# X10_-_Main_Board_RevB.net
KiCad netlist of a schematic drawn in EAGLE
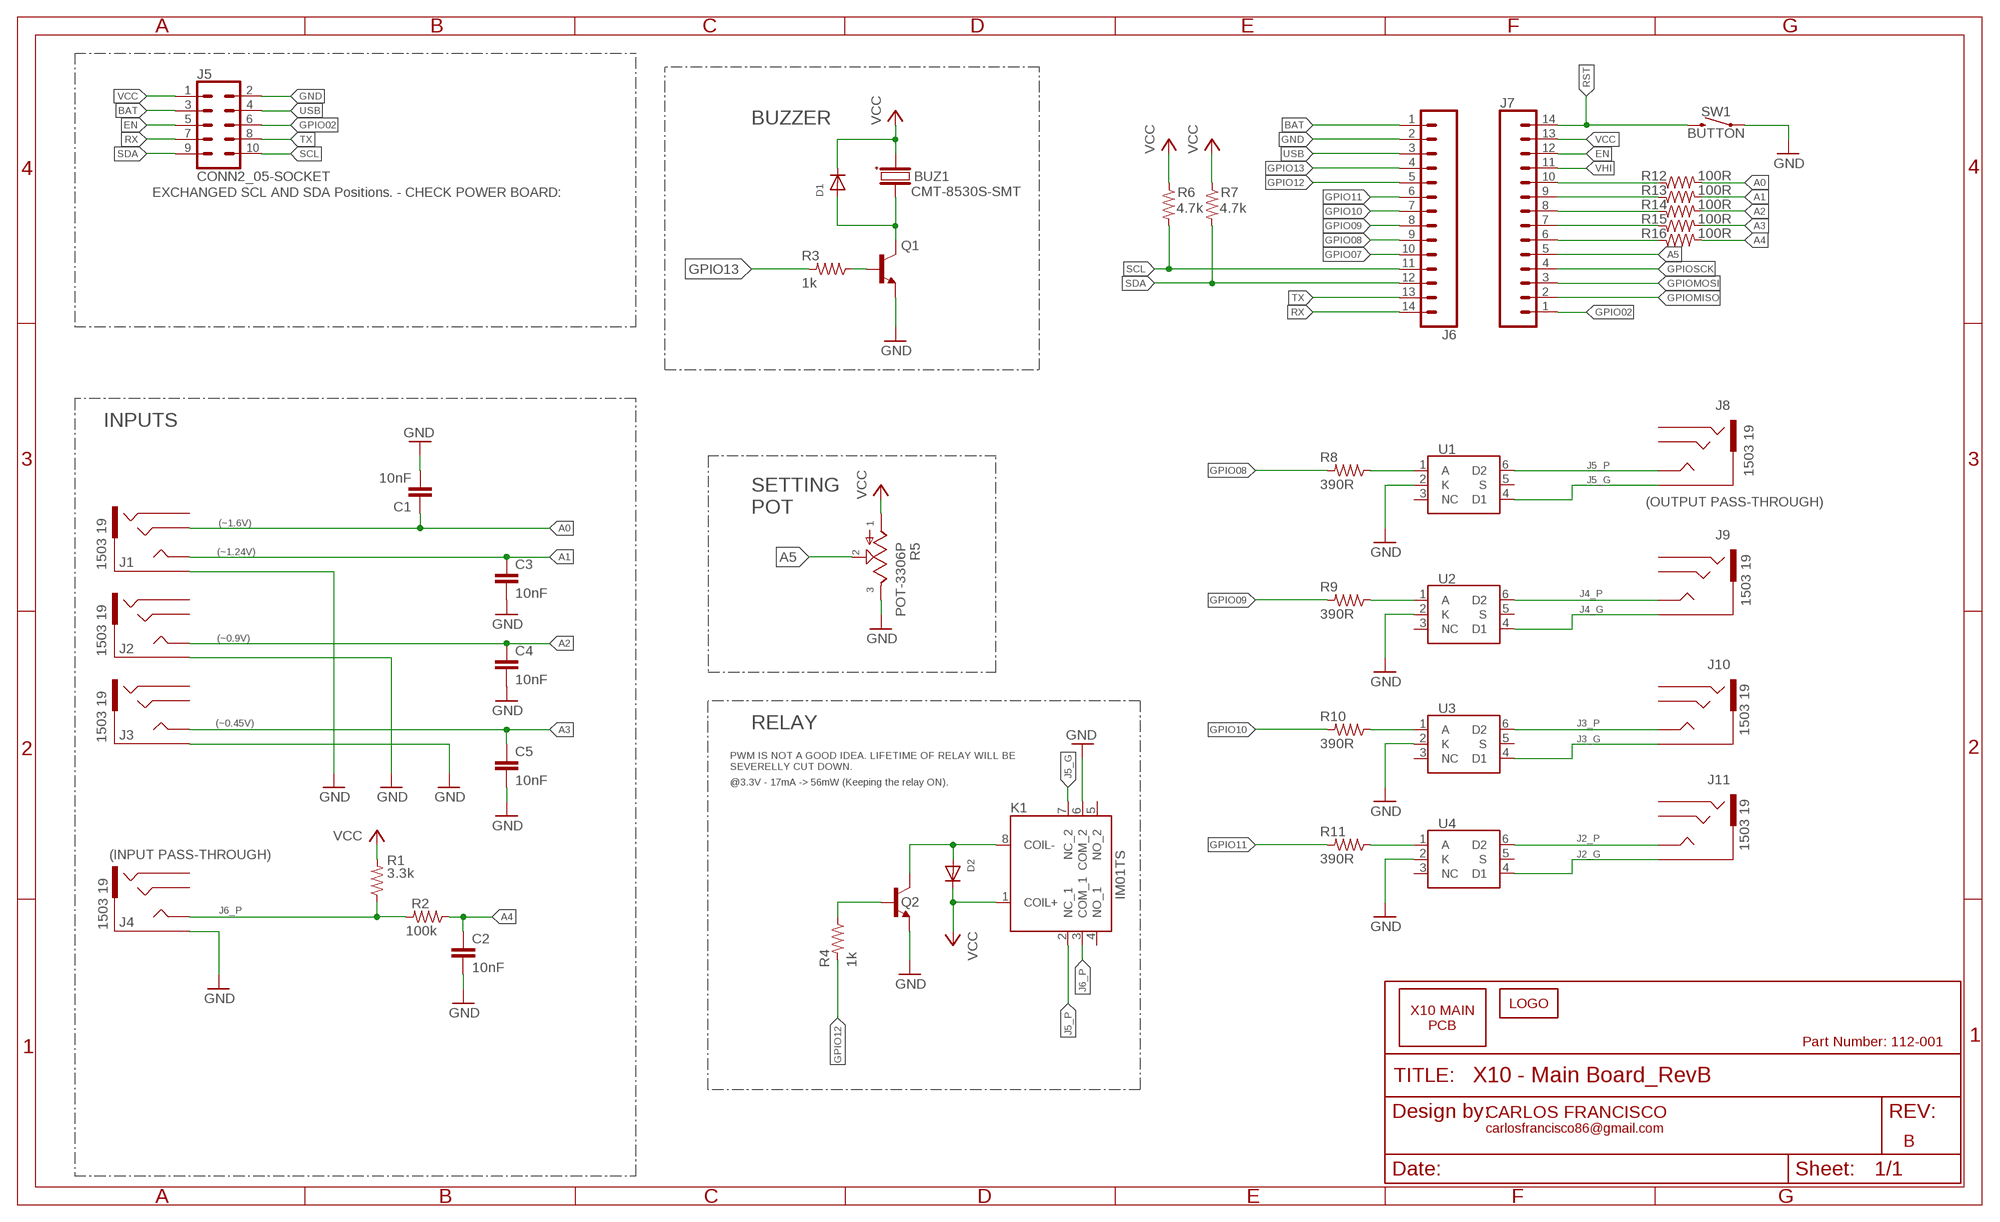
[diagram p0: schematic, sheet 1]

(export (version "E")
  (design (tool "Eeschema 10.0.6"))
  (components
    (comp (ref "BUZ1")
      (value "CMT-8530S-SMT")
      (footprint "eagle-import:CMT8530SSMTTR")
      (libsource (lib "eagle-import") (part "BUZZER-CMT-8530S-SMT-TR"))
    )
    (comp (ref "C1")
      (value "10nF")
      (footprint "eagle-import:CAPC1608X85")
      (fields (field (name "MFR") "Samsung"))
      (libsource (lib "eagle-import") (part "C-0603-10NF-50V-X7R"))
    )
    (comp (ref "C2")
      (value "10nF")
      (footprint "eagle-import:CAPC1608X85")
      (fields (field (name "MFR") "Samsung"))
      (libsource (lib "eagle-import") (part "C-0603-10NF-50V-X7R"))
    )
    (comp (ref "C3")
      (value "10nF")
      (footprint "eagle-import:CAPC1608X85")
      (fields (field (name "MFR") "Samsung"))
      (libsource (lib "eagle-import") (part "C-0603-10NF-50V-X7R"))
    )
    (comp (ref "C4")
      (value "10nF")
      (footprint "eagle-import:CAPC1608X85")
      (fields (field (name "MFR") "Samsung"))
      (libsource (lib "eagle-import") (part "C-0603-10NF-50V-X7R"))
    )
    (comp (ref "C5")
      (value "10nF")
      (footprint "eagle-import:CAPC1608X85")
      (fields (field (name "MFR") "Samsung"))
      (libsource (lib "eagle-import") (part "C-0603-10NF-50V-X7R"))
    )
    (comp (ref "D1")
      (value "DIODE-SOD-123")
      (footprint "eagle-import:SOD-123")
      (libsource (lib "eagle-import") (part "DIODE-SOD-123"))
    )
    (comp (ref "D2")
      (value "DIODE-SOD-123")
      (footprint "eagle-import:SOD-123")
      (libsource (lib "eagle-import") (part "DIODE-SOD-123"))
    )
    (comp (ref "J1")
      (value "1503 19")
      (footprint "eagle-import:1503-19")
      (fields (field (name "MFR") "Lumberg"))
      (libsource (lib "eagle-import") (part "STEREO_JACK-1503-19"))
    )
    (comp (ref "J2")
      (value "1503 19")
      (footprint "eagle-import:1503-19")
      (fields (field (name "MFR") "Lumberg"))
      (libsource (lib "eagle-import") (part "STEREO_JACK-1503-19"))
    )
    (comp (ref "J3")
      (value "1503 19")
      (footprint "eagle-import:1503-19")
      (fields (field (name "MFR") "Lumberg"))
      (libsource (lib "eagle-import") (part "STEREO_JACK-1503-19"))
    )
    (comp (ref "J4")
      (value "1503 19")
      (footprint "eagle-import:1503-19")
      (fields (field (name "MFR") "Lumberg"))
      (libsource (lib "eagle-import") (part "STEREO_JACK-1503-19"))
    )
    (comp (ref "J5")
      (value "CONN2_05-SOCKET")
      (footprint "eagle-import:2X5_SOCKET")
      (libsource (lib "eagle-import") (part "CONN2_05-SOCKET"))
    )
    (comp (ref "J6")
      (value "CONN_14")
      (footprint "eagle-import:1X14")
      (libsource (lib "eagle-import") (part "CONN_14"))
    )
    (comp (ref "J7")
      (value "CONN_14")
      (footprint "eagle-import:1X14")
      (libsource (lib "eagle-import") (part "CONN_14"))
    )
    (comp (ref "J8")
      (value "1503 19")
      (footprint "eagle-import:1503-19")
      (fields (field (name "MFR") "Lumberg"))
      (libsource (lib "eagle-import") (part "STEREO_JACK-1503-19"))
    )
    (comp (ref "J9")
      (value "1503 19")
      (footprint "eagle-import:1503-19")
      (fields (field (name "MFR") "Lumberg"))
      (libsource (lib "eagle-import") (part "STEREO_JACK-1503-19"))
    )
    (comp (ref "J10")
      (value "1503 19")
      (footprint "eagle-import:1503-19")
      (fields (field (name "MFR") "Lumberg"))
      (libsource (lib "eagle-import") (part "STEREO_JACK-1503-19"))
    )
    (comp (ref "J11")
      (value "1503 19")
      (footprint "eagle-import:1503-19")
      (fields (field (name "MFR") "Lumberg"))
      (libsource (lib "eagle-import") (part "STEREO_JACK-1503-19"))
    )
    (comp (ref "K1")
      (value "IM01TS")
      (footprint "eagle-import:IM03TS114620378")
      (fields (field (name "MFR") "TE Connectivity"))
      (libsource (lib "eagle-import") (part "IM02TS"))
    )
    (comp (ref "LOGO1")
      (value "LOGO-10MM")
      (footprint "eagle-import:LOGO_10MM")
      (libsource (lib "eagle-import") (part "LOGO-10MM"))
    )
    (comp (ref "PCB1")
      (value "X10_MAIN_PCB-X10_MAIN")
      (footprint "eagle-import:X10_MAIN_PCB")
      (libsource (lib "eagle-import") (part "X10_MAIN_PCB-X10_MAIN"))
    )
    (comp (ref "Q1")
      (value "NPN-SOT-23")
      (footprint "eagle-import:SOT-23")
      (libsource (lib "eagle-import") (part "NPN-SOT-23"))
    )
    (comp (ref "Q2")
      (value "NPN-SOT-23")
      (footprint "eagle-import:SOT-23")
      (libsource (lib "eagle-import") (part "NPN-SOT-23"))
    )
    (comp (ref "R1")
      (value "3.3k")
      (footprint "eagle-import:R0603")
      (fields (field (name "MFR") "Yageo"))
      (libsource (lib "eagle-import") (part "R-0603-3.3K-1%"))
    )
    (comp (ref "R2")
      (value "100k")
      (footprint "eagle-import:R0603")
      (fields (field (name "MFR") "Yageo"))
      (libsource (lib "eagle-import") (part "R-0603-100K-1%"))
    )
    (comp (ref "R3")
      (value "1k")
      (footprint "eagle-import:R0603")
      (fields (field (name "MFR") "Yageo"))
      (libsource (lib "eagle-import") (part "R-0603-1K-1%"))
    )
    (comp (ref "R4")
      (value "1k")
      (footprint "eagle-import:R0603")
      (fields (field (name "MFR") "Yageo"))
      (libsource (lib "eagle-import") (part "R-0603-1K-1%"))
    )
    (comp (ref "R5")
      (value "POT-3306P")
      (footprint "eagle-import:3306P1103")
      (libsource (lib "eagle-import") (part "POT-3306P"))
    )
    (comp (ref "R6")
      (value "4.7k")
      (footprint "eagle-import:R0603")
      (fields (field (name "MFR") "Yageo"))
      (libsource (lib "eagle-import") (part "R-0603-390R-1%"))
    )
    (comp (ref "R7")
      (value "4.7k")
      (footprint "eagle-import:R0603")
      (fields (field (name "MFR") "Yageo"))
      (libsource (lib "eagle-import") (part "R-0603-390R-1%"))
    )
    (comp (ref "R8")
      (value "390R")
      (footprint "eagle-import:R0603")
      (fields (field (name "MFR") "Yageo"))
      (libsource (lib "eagle-import") (part "R-0603-390R-1%"))
    )
    (comp (ref "R9")
      (value "390R")
      (footprint "eagle-import:R0603")
      (fields (field (name "MFR") "Yageo"))
      (libsource (lib "eagle-import") (part "R-0603-390R-1%"))
    )
    (comp (ref "R10")
      (value "390R")
      (footprint "eagle-import:R0603")
      (fields (field (name "MFR") "Yageo"))
      (libsource (lib "eagle-import") (part "R-0603-390R-1%"))
    )
    (comp (ref "R11")
      (value "390R")
      (footprint "eagle-import:R0603")
      (fields (field (name "MFR") "Yageo"))
      (libsource (lib "eagle-import") (part "R-0603-390R-1%"))
    )
    (comp (ref "R12")
      (value "100R")
      (footprint "eagle-import:R0603")
      (fields (field (name "MFR") "Yageo"))
      (libsource (lib "eagle-import") (part "R-0603-100R-1%"))
    )
    (comp (ref "R13")
      (value "100R")
      (footprint "eagle-import:R0603")
      (fields (field (name "MFR") "Yageo"))
      (libsource (lib "eagle-import") (part "R-0603-100R-1%"))
    )
    (comp (ref "R14")
      (value "100R")
      (footprint "eagle-import:R0603")
      (fields (field (name "MFR") "Yageo"))
      (libsource (lib "eagle-import") (part "R-0603-100R-1%"))
    )
    (comp (ref "R15")
      (value "100R")
      (footprint "eagle-import:R0603")
      (fields (field (name "MFR") "Yageo"))
      (libsource (lib "eagle-import") (part "R-0603-100R-1%"))
    )
    (comp (ref "R16")
      (value "100R")
      (footprint "eagle-import:R0603")
      (fields (field (name "MFR") "Yageo"))
      (libsource (lib "eagle-import") (part "R-0603-100R-1%"))
    )
    (comp (ref "SW1")
      (value "BUTTON")
      (footprint "eagle-import:SERIES95C_RA")
      (libsource (lib "eagle-import") (part "BUTTON"))
    )
    (comp (ref "U1")
      (value "LH1500AT")
      (footprint "eagle-import:DIP762W47P254L880H410Q6N")
      (fields (field (name "MFR") "Vishay"))
      (libsource (lib "eagle-import") (part "SSR-LH1500AT"))
    )
    (comp (ref "U2")
      (value "LH1500AT")
      (footprint "eagle-import:DIP762W47P254L880H410Q6N")
      (fields (field (name "MFR") "Vishay"))
      (libsource (lib "eagle-import") (part "SSR-LH1500AT"))
    )
    (comp (ref "U3")
      (value "LH1500AT")
      (footprint "eagle-import:DIP762W47P254L880H410Q6N")
      (fields (field (name "MFR") "Vishay"))
      (libsource (lib "eagle-import") (part "SSR-LH1500AT"))
    )
    (comp (ref "U4")
      (value "LH1500AT")
      (footprint "eagle-import:DIP762W47P254L880H410Q6N")
      (fields (field (name "MFR") "Vishay"))
      (libsource (lib "eagle-import") (part "SSR-LH1500AT"))
    )
  )
  (nets
    (net (code "1") (name "/J2_G") (class "Default")
      (node (ref "J11") (pin "1") (pinfunction "1_1") (pintype "bidirectional"))
      (node (ref "U4") (pin "4") (pinfunction "D1_4") (pintype "bidirectional"))
    )
    (net (code "2") (name "/J2_P") (class "Default")
      (node (ref "J11") (pin "4") (pinfunction "4_4") (pintype "bidirectional"))
      (node (ref "J11") (pin "5") (pinfunction "4_5") (pintype "bidirectional"))
      (node (ref "U4") (pin "6") (pinfunction "D2_6") (pintype "bidirectional"))
    )
    (net (code "3") (name "/J3_G") (class "Default")
      (node (ref "J10") (pin "1") (pinfunction "1_1") (pintype "bidirectional"))
      (node (ref "U3") (pin "4") (pinfunction "D1_4") (pintype "bidirectional"))
    )
    (net (code "4") (name "/J3_P") (class "Default")
      (node (ref "J10") (pin "4") (pinfunction "4_4") (pintype "bidirectional"))
      (node (ref "J10") (pin "5") (pinfunction "4_5") (pintype "bidirectional"))
      (node (ref "U3") (pin "6") (pinfunction "D2_6") (pintype "bidirectional"))
    )
    (net (code "5") (name "/J4_G") (class "Default")
      (node (ref "J9") (pin "1") (pinfunction "1_1") (pintype "bidirectional"))
      (node (ref "U2") (pin "4") (pinfunction "D1_4") (pintype "bidirectional"))
    )
    (net (code "6") (name "/J4_P") (class "Default")
      (node (ref "J9") (pin "4") (pinfunction "4_4") (pintype "bidirectional"))
      (node (ref "J9") (pin "5") (pinfunction "4_5") (pintype "bidirectional"))
      (node (ref "U2") (pin "6") (pinfunction "D2_6") (pintype "bidirectional"))
    )
    (net (code "7") (name "A0") (class "Default")
      (node (ref "C1") (pin "1") (pinfunction "1_1") (pintype "passive"))
      (node (ref "J1") (pin "3") (pinfunction "3_3") (pintype "bidirectional"))
      (node (ref "R12") (pin "1") (pinfunction "1_1") (pintype "passive"))
    )
    (net (code "8") (name "A1") (class "Default")
      (node (ref "C3") (pin "1") (pinfunction "1_1") (pintype "passive"))
      (node (ref "J1") (pin "4") (pinfunction "4_4") (pintype "bidirectional"))
      (node (ref "J1") (pin "5") (pinfunction "4_5") (pintype "bidirectional"))
      (node (ref "R13") (pin "1") (pinfunction "1_1") (pintype "passive"))
    )
    (net (code "9") (name "A2") (class "Default")
      (node (ref "C4") (pin "1") (pinfunction "1_1") (pintype "passive"))
      (node (ref "J2") (pin "4") (pinfunction "4_4") (pintype "bidirectional"))
      (node (ref "J2") (pin "5") (pinfunction "4_5") (pintype "bidirectional"))
      (node (ref "R14") (pin "1") (pinfunction "1_1") (pintype "passive"))
    )
    (net (code "10") (name "A3") (class "Default")
      (node (ref "C5") (pin "1") (pinfunction "1_1") (pintype "passive"))
      (node (ref "J3") (pin "4") (pinfunction "4_4") (pintype "bidirectional"))
      (node (ref "J3") (pin "5") (pinfunction "4_5") (pintype "bidirectional"))
      (node (ref "R15") (pin "1") (pinfunction "1_1") (pintype "passive"))
    )
    (net (code "11") (name "A4") (class "Default")
      (node (ref "C2") (pin "1") (pinfunction "1_1") (pintype "passive"))
      (node (ref "R16") (pin "1") (pinfunction "1_1") (pintype "passive"))
      (node (ref "R2") (pin "2") (pinfunction "2_2") (pintype "passive"))
    )
    (net (code "12") (name "A5") (class "Default")
      (node (ref "J7") (pin "5") (pinfunction "5_5") (pintype "passive"))
      (node (ref "R5") (pin "2") (pinfunction "2_2") (pintype "passive"))
    )
    (net (code "13") (name "BAT") (class "Default")
      (node (ref "J5") (pin "3") (pinfunction "3_3") (pintype "passive"))
      (node (ref "J6") (pin "1") (pinfunction "1_1") (pintype "passive"))
    )
    (net (code "14") (name "EN") (class "Default")
      (node (ref "J5") (pin "5") (pinfunction "5_5") (pintype "passive"))
      (node (ref "J7") (pin "12") (pinfunction "12_12") (pintype "passive"))
    )
    (net (code "15") (name "GND") (class "Default")
      (node (ref "C1") (pin "2") (pinfunction "2_2") (pintype "passive"))
      (node (ref "C2") (pin "2") (pinfunction "2_2") (pintype "passive"))
      (node (ref "C3") (pin "2") (pinfunction "2_2") (pintype "passive"))
      (node (ref "C4") (pin "2") (pinfunction "2_2") (pintype "passive"))
      (node (ref "C5") (pin "2") (pinfunction "2_2") (pintype "passive"))
      (node (ref "J1") (pin "1") (pinfunction "1_1") (pintype "bidirectional"))
      (node (ref "J2") (pin "1") (pinfunction "1_1") (pintype "bidirectional"))
      (node (ref "J3") (pin "1") (pinfunction "1_1") (pintype "bidirectional"))
      (node (ref "J4") (pin "1") (pinfunction "1_1") (pintype "bidirectional"))
      (node (ref "J5") (pin "2") (pinfunction "2_2") (pintype "passive"))
      (node (ref "J6") (pin "2") (pinfunction "2_2") (pintype "passive"))
      (node (ref "K1") (pin "6") (pinfunction "COM_2_6") (pintype "bidirectional"))
      (node (ref "Q1") (pin "E") (pinfunction "E_E") (pintype "passive"))
      (node (ref "Q2") (pin "E") (pinfunction "E_E") (pintype "passive"))
      (node (ref "R5") (pin "3") (pinfunction "3_3") (pintype "passive"))
      (node (ref "SW1") (pin "T1") (pinfunction "1_T1") (pintype "passive"))
      (node (ref "U1") (pin "2") (pinfunction "K_2") (pintype "bidirectional"))
      (node (ref "U2") (pin "2") (pinfunction "K_2") (pintype "bidirectional"))
      (node (ref "U3") (pin "2") (pinfunction "K_2") (pintype "bidirectional"))
      (node (ref "U4") (pin "2") (pinfunction "K_2") (pintype "bidirectional"))
    )
    (net (code "16") (name "GPIO02") (class "Default")
      (node (ref "J5") (pin "6") (pinfunction "6_6") (pintype "passive"))
      (node (ref "J7") (pin "1") (pinfunction "1_1") (pintype "passive"))
    )
    (net (code "17") (name "GPIO07") (class "Default")
      (node (ref "J6") (pin "10") (pinfunction "10_10") (pintype "passive"))
    )
    (net (code "18") (name "GPIO08") (class "Default")
      (node (ref "J6") (pin "9") (pinfunction "9_9") (pintype "passive"))
      (node (ref "R8") (pin "1") (pinfunction "1_1") (pintype "passive"))
    )
    (net (code "19") (name "GPIO09") (class "Default")
      (node (ref "J6") (pin "8") (pinfunction "8_8") (pintype "passive"))
      (node (ref "R9") (pin "1") (pinfunction "1_1") (pintype "passive"))
    )
    (net (code "20") (name "GPIO10") (class "Default")
      (node (ref "J6") (pin "7") (pinfunction "7_7") (pintype "passive"))
      (node (ref "R10") (pin "1") (pinfunction "1_1") (pintype "passive"))
    )
    (net (code "21") (name "GPIO11") (class "Default")
      (node (ref "J6") (pin "6") (pinfunction "6_6") (pintype "passive"))
      (node (ref "R11") (pin "1") (pinfunction "1_1") (pintype "passive"))
    )
    (net (code "22") (name "GPIO12") (class "Default")
      (node (ref "J6") (pin "5") (pinfunction "5_5") (pintype "passive"))
      (node (ref "R4") (pin "1") (pinfunction "1_1") (pintype "passive"))
    )
    (net (code "23") (name "GPIO13") (class "Default")
      (node (ref "J6") (pin "4") (pinfunction "4_4") (pintype "passive"))
      (node (ref "R3") (pin "1") (pinfunction "1_1") (pintype "passive"))
    )
    (net (code "24") (name "GPIOMISO") (class "Default")
      (node (ref "J7") (pin "2") (pinfunction "2_2") (pintype "passive"))
    )
    (net (code "25") (name "GPIOMOSI") (class "Default")
      (node (ref "J7") (pin "3") (pinfunction "3_3") (pintype "passive"))
    )
    (net (code "26") (name "GPIOSCK") (class "Default")
      (node (ref "J7") (pin "4") (pinfunction "4_4") (pintype "passive"))
    )
    (net (code "27") (name "J5_G") (class "Default")
      (node (ref "J8") (pin "1") (pinfunction "1_1") (pintype "bidirectional"))
      (node (ref "K1") (pin "7") (pinfunction "NC_2_7") (pintype "bidirectional"))
      (node (ref "U1") (pin "4") (pinfunction "D1_4") (pintype "bidirectional"))
    )
    (net (code "28") (name "J5_P") (class "Default")
      (node (ref "J8") (pin "4") (pinfunction "4_4") (pintype "bidirectional"))
      (node (ref "J8") (pin "5") (pinfunction "4_5") (pintype "bidirectional"))
      (node (ref "K1") (pin "2") (pinfunction "NC_1_2") (pintype "bidirectional"))
      (node (ref "U1") (pin "6") (pinfunction "D2_6") (pintype "bidirectional"))
    )
    (net (code "29") (name "J6_P") (class "Default")
      (node (ref "J4") (pin "4") (pinfunction "4_4") (pintype "bidirectional"))
      (node (ref "J4") (pin "5") (pinfunction "4_5") (pintype "bidirectional"))
      (node (ref "K1") (pin "3") (pinfunction "COM_1_3") (pintype "bidirectional"))
      (node (ref "R1") (pin "2") (pinfunction "2_2") (pintype "passive"))
      (node (ref "R2") (pin "1") (pinfunction "1_1") (pintype "passive"))
    )
    (net (code "30") (name "Net-(BUZ1--)") (class "Default")
      (node (ref "BUZ1") (pin "3") (pinfunction "-_3") (pintype "passive"))
      (node (ref "D1") (pin "A") (pinfunction "A_A") (pintype "passive"))
      (node (ref "Q1") (pin "C") (pinfunction "C_C") (pintype "passive"))
    )
    (net (code "31") (name "Net-(J7-Pad6)") (class "Default")
      (node (ref "J7") (pin "6") (pinfunction "6_6") (pintype "passive"))
      (node (ref "R16") (pin "2") (pinfunction "2_2") (pintype "passive"))
    )
    (net (code "32") (name "Net-(J7-Pad7)") (class "Default")
      (node (ref "J7") (pin "7") (pinfunction "7_7") (pintype "passive"))
      (node (ref "R15") (pin "2") (pinfunction "2_2") (pintype "passive"))
    )
    (net (code "33") (name "Net-(J7-Pad8)") (class "Default")
      (node (ref "J7") (pin "8") (pinfunction "8_8") (pintype "passive"))
      (node (ref "R14") (pin "2") (pinfunction "2_2") (pintype "passive"))
    )
    (net (code "34") (name "Net-(J7-Pad9)") (class "Default")
      (node (ref "J7") (pin "9") (pinfunction "9_9") (pintype "passive"))
      (node (ref "R13") (pin "2") (pinfunction "2_2") (pintype "passive"))
    )
    (net (code "35") (name "Net-(J7-Pad10)") (class "Default")
      (node (ref "J7") (pin "10") (pinfunction "10_10") (pintype "passive"))
      (node (ref "R12") (pin "2") (pinfunction "2_2") (pintype "passive"))
    )
    (net (code "36") (name "Net-(K1-COIL-)") (class "Default")
      (node (ref "D2") (pin "A") (pinfunction "A_A") (pintype "passive"))
      (node (ref "K1") (pin "8") (pinfunction "COIL-_8") (pintype "bidirectional"))
      (node (ref "Q2") (pin "C") (pinfunction "C_C") (pintype "passive"))
    )
    (net (code "37") (name "Net-(Q1-PadB)") (class "Default")
      (node (ref "Q1") (pin "B") (pinfunction "B_B") (pintype "passive"))
      (node (ref "R3") (pin "2") (pinfunction "2_2") (pintype "passive"))
    )
    (net (code "38") (name "Net-(Q2-PadB)") (class "Default")
      (node (ref "Q2") (pin "B") (pinfunction "B_B") (pintype "passive"))
      (node (ref "R4") (pin "2") (pinfunction "2_2") (pintype "passive"))
    )
    (net (code "39") (name "Net-(U1-A)") (class "Default")
      (node (ref "R8") (pin "2") (pinfunction "2_2") (pintype "passive"))
      (node (ref "U1") (pin "1") (pinfunction "A_1") (pintype "bidirectional"))
    )
    (net (code "40") (name "Net-(U2-A)") (class "Default")
      (node (ref "R9") (pin "2") (pinfunction "2_2") (pintype "passive"))
      (node (ref "U2") (pin "1") (pinfunction "A_1") (pintype "bidirectional"))
    )
    (net (code "41") (name "Net-(U3-A)") (class "Default")
      (node (ref "R10") (pin "2") (pinfunction "2_2") (pintype "passive"))
      (node (ref "U3") (pin "1") (pinfunction "A_1") (pintype "bidirectional"))
    )
    (net (code "42") (name "Net-(U4-A)") (class "Default")
      (node (ref "R11") (pin "2") (pinfunction "2_2") (pintype "passive"))
      (node (ref "U4") (pin "1") (pinfunction "A_1") (pintype "bidirectional"))
    )
    (net (code "43") (name "RST") (class "Default")
      (node (ref "J7") (pin "14") (pinfunction "14_14") (pintype "passive"))
      (node (ref "SW1") (pin "T2") (pinfunction "2_T2") (pintype "passive"))
    )
    (net (code "44") (name "RX") (class "Default")
      (node (ref "J5") (pin "7") (pinfunction "7_7") (pintype "passive"))
      (node (ref "J6") (pin "14") (pinfunction "14_14") (pintype "passive"))
    )
    (net (code "45") (name "SCL") (class "Default")
      (node (ref "J5") (pin "10") (pinfunction "10_10") (pintype "passive"))
      (node (ref "J6") (pin "11") (pinfunction "11_11") (pintype "passive"))
      (node (ref "R6") (pin "1") (pinfunction "1_1") (pintype "passive"))
    )
    (net (code "46") (name "SDA") (class "Default")
      (node (ref "J5") (pin "9") (pinfunction "9_9") (pintype "passive"))
      (node (ref "J6") (pin "12") (pinfunction "12_12") (pintype "passive"))
      (node (ref "R7") (pin "1") (pinfunction "1_1") (pintype "passive"))
    )
    (net (code "47") (name "TX") (class "Default")
      (node (ref "J5") (pin "8") (pinfunction "8_8") (pintype "passive"))
      (node (ref "J6") (pin "13") (pinfunction "13_13") (pintype "passive"))
    )
    (net (code "48") (name "USB") (class "Default")
      (node (ref "J5") (pin "4") (pinfunction "4_4") (pintype "passive"))
      (node (ref "J6") (pin "3") (pinfunction "3_3") (pintype "passive"))
    )
    (net (code "49") (name "VCC") (class "Default")
      (node (ref "BUZ1") (pin "2") (pinfunction "+_2") (pintype "passive"))
      (node (ref "D1") (pin "C") (pinfunction "C_C") (pintype "passive"))
      (node (ref "D2") (pin "C") (pinfunction "C_C") (pintype "passive"))
      (node (ref "J5") (pin "1") (pinfunction "1_1") (pintype "passive"))
      (node (ref "J7") (pin "13") (pinfunction "13_13") (pintype "passive"))
      (node (ref "K1") (pin "1") (pinfunction "COIL+_1") (pintype "bidirectional"))
      (node (ref "R1") (pin "1") (pinfunction "1_1") (pintype "passive"))
      (node (ref "R5") (pin "1") (pinfunction "1_1") (pintype "passive"))
      (node (ref "R6") (pin "2") (pinfunction "2_2") (pintype "passive"))
      (node (ref "R7") (pin "2") (pinfunction "2_2") (pintype "passive"))
    )
    (net (code "50") (name "VHI") (class "Default")
      (node (ref "J7") (pin "11") (pinfunction "11_11") (pintype "passive"))
    )
    (net (code "51") (name "unconnected-(J1-Pad2)") (class "Default")
      (node (ref "J1") (pin "2") (pinfunction "2_2") (pintype "bidirectional"))
    )
    (net (code "52") (name "unconnected-(J2-Pad2)") (class "Default")
      (node (ref "J2") (pin "2") (pinfunction "2_2") (pintype "bidirectional"))
    )
    (net (code "53") (name "unconnected-(J2-Pad3)") (class "Default")
      (node (ref "J2") (pin "3") (pinfunction "3_3") (pintype "bidirectional"))
    )
    (net (code "54") (name "unconnected-(J3-Pad2)") (class "Default")
      (node (ref "J3") (pin "2") (pinfunction "2_2") (pintype "bidirectional"))
    )
    (net (code "55") (name "unconnected-(J3-Pad3)") (class "Default")
      (node (ref "J3") (pin "3") (pinfunction "3_3") (pintype "bidirectional"))
    )
    (net (code "56") (name "unconnected-(J4-Pad2)") (class "Default")
      (node (ref "J4") (pin "2") (pinfunction "2_2") (pintype "bidirectional"))
    )
    (net (code "57") (name "unconnected-(J4-Pad3)") (class "Default")
      (node (ref "J4") (pin "3") (pinfunction "3_3") (pintype "bidirectional"))
    )
    (net (code "58") (name "unconnected-(J8-Pad2)") (class "Default")
      (node (ref "J8") (pin "2") (pinfunction "2_2") (pintype "bidirectional"))
    )
    (net (code "59") (name "unconnected-(J8-Pad3)") (class "Default")
      (node (ref "J8") (pin "3") (pinfunction "3_3") (pintype "bidirectional"))
    )
    (net (code "60") (name "unconnected-(J9-Pad2)") (class "Default")
      (node (ref "J9") (pin "2") (pinfunction "2_2") (pintype "bidirectional"))
    )
    (net (code "61") (name "unconnected-(J9-Pad3)") (class "Default")
      (node (ref "J9") (pin "3") (pinfunction "3_3") (pintype "bidirectional"))
    )
    (net (code "62") (name "unconnected-(J10-Pad2)") (class "Default")
      (node (ref "J10") (pin "2") (pinfunction "2_2") (pintype "bidirectional"))
    )
    (net (code "63") (name "unconnected-(J10-Pad3)") (class "Default")
      (node (ref "J10") (pin "3") (pinfunction "3_3") (pintype "bidirectional"))
    )
    (net (code "64") (name "unconnected-(J11-Pad2)") (class "Default")
      (node (ref "J11") (pin "2") (pinfunction "2_2") (pintype "bidirectional"))
    )
    (net (code "65") (name "unconnected-(J11-Pad3)") (class "Default")
      (node (ref "J11") (pin "3") (pinfunction "3_3") (pintype "bidirectional"))
    )
    (net (code "66") (name "unconnected-(K1-NO_1-Pad4)") (class "Default")
      (node (ref "K1") (pin "4") (pinfunction "NO_1_4") (pintype "bidirectional"))
    )
    (net (code "67") (name "unconnected-(K1-NO_2-Pad5)") (class "Default")
      (node (ref "K1") (pin "5") (pinfunction "NO_2_5") (pintype "bidirectional"))
    )
    (net (code "68") (name "unconnected-(U1-NC-Pad3)") (class "Default")
      (node (ref "U1") (pin "3") (pinfunction "NC_3") (pintype "no_connect"))
    )
    (net (code "69") (name "unconnected-(U1-S-Pad5)") (class "Default")
      (node (ref "U1") (pin "5") (pinfunction "S_5") (pintype "bidirectional"))
    )
    (net (code "70") (name "unconnected-(U2-NC-Pad3)") (class "Default")
      (node (ref "U2") (pin "3") (pinfunction "NC_3") (pintype "no_connect"))
    )
    (net (code "71") (name "unconnected-(U2-S-Pad5)") (class "Default")
      (node (ref "U2") (pin "5") (pinfunction "S_5") (pintype "bidirectional"))
    )
    (net (code "72") (name "unconnected-(U3-NC-Pad3)") (class "Default")
      (node (ref "U3") (pin "3") (pinfunction "NC_3") (pintype "no_connect"))
    )
    (net (code "73") (name "unconnected-(U3-S-Pad5)") (class "Default")
      (node (ref "U3") (pin "5") (pinfunction "S_5") (pintype "bidirectional"))
    )
    (net (code "74") (name "unconnected-(U4-NC-Pad3)") (class "Default")
      (node (ref "U4") (pin "3") (pinfunction "NC_3") (pintype "no_connect"))
    )
    (net (code "75") (name "unconnected-(U4-S-Pad5)") (class "Default")
      (node (ref "U4") (pin "5") (pinfunction "S_5") (pintype "bidirectional"))
    )
  )
)
